# TLM_002_SRC.net
KiCad netlist of a schematic drawn in Altium Designer
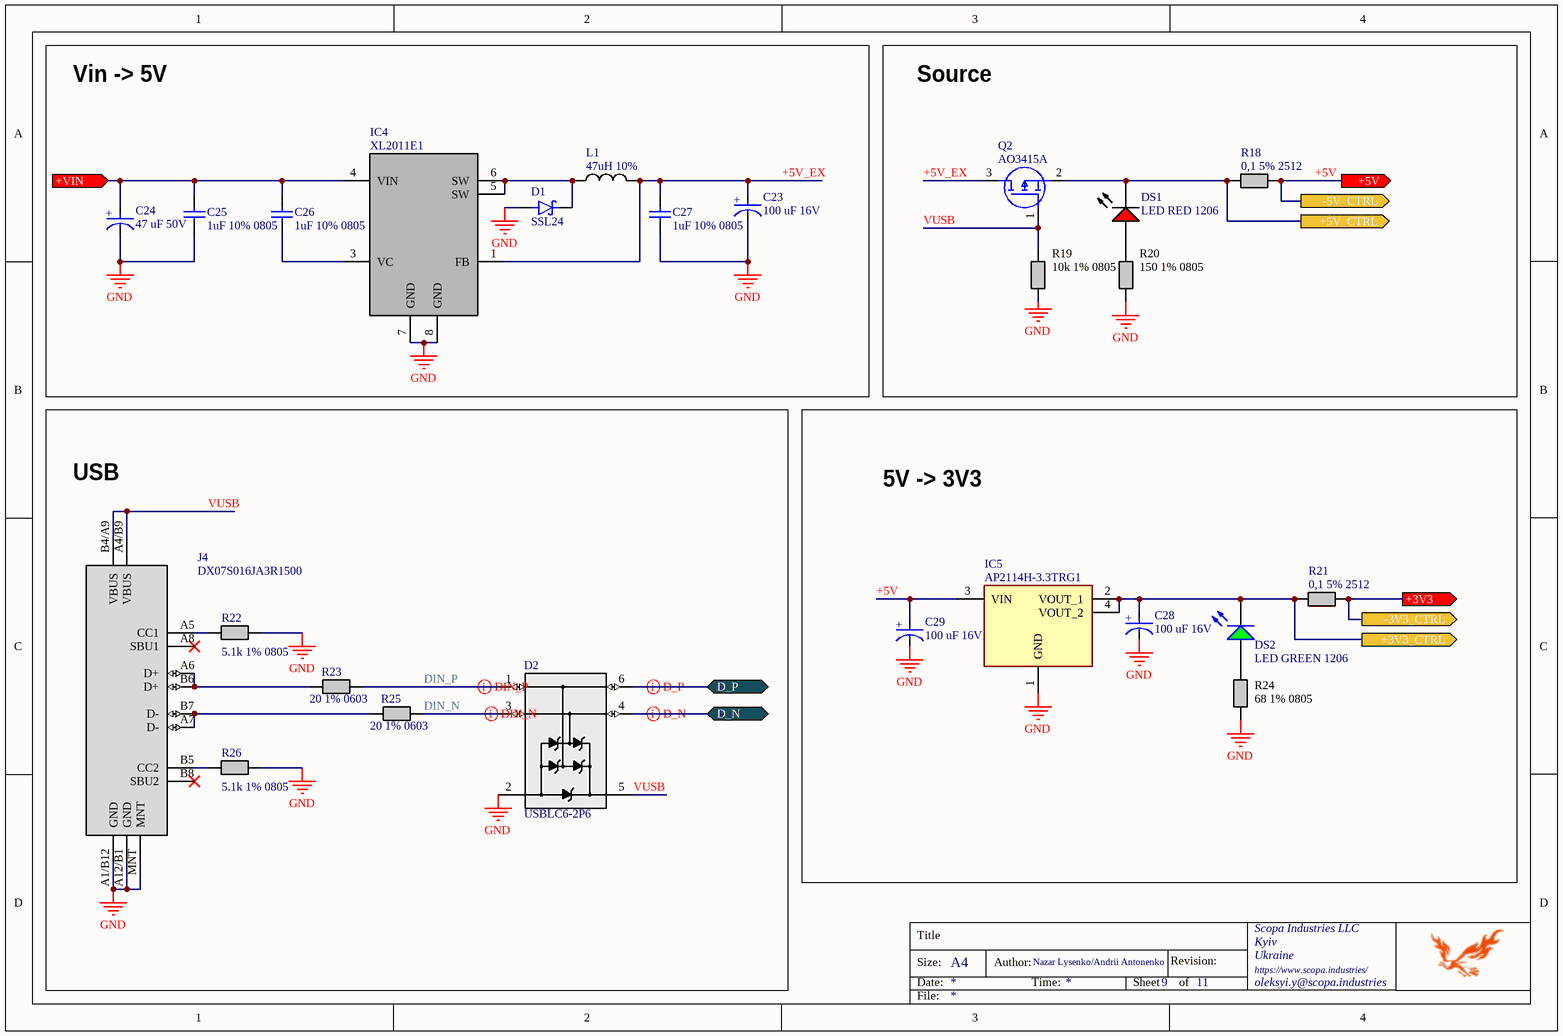
[diagram p0: TLM_002_SRC.SchDoc]

(export (version "E")
  (design (tool "Eeschema 10.0.6"))
  (components
    (comp (ref "C23")
      (value "100 uF 16V")
      (footprint "FP-ZLG6_3X11-MFG")
      (description "CAP ALUM 100UF 16V RADIAL")
      (fields (field (name "TOLERANCE") "20%"))
      (libsource (lib "Altium Content Vault") (part "a00bbbee19879c290e62620ae7e47b1"))
    )
    (comp (ref "C24")
      (value "47 uF 50V")
      (footprint "FP-ZLG6_3X11-MFG")
      (description "CAP ALUM 47UF 50V RADIAL")
      (fields (field (name "TOLERANCE") "20%"))
      (libsource (lib "Altium Content Vault") (part "a00bbbee19879c290e62620ae7e47b1"))
    )
    (comp (ref "C25")
      (value "1uF 10% 0805")
      (footprint "CAPC2013X145X50NL20T20")
      (fields (field (name "PART NUMBER") "VJ0805Y105KXQRW1BC") (field (name "MANUFACTURER") "Vitramon"))
      (libsource (lib "Altium Content Vault") (part "CAP"))
    )
    (comp (ref "C26")
      (value "1uF 10% 0805")
      (footprint "CAPC2013X145X50NL20T20")
      (fields (field (name "PART NUMBER") "VJ0805Y105KXQRW1BC") (field (name "MANUFACTURER") "Vitramon"))
      (libsource (lib "Altium Content Vault") (part "CAP"))
    )
    (comp (ref "C27")
      (value "1uF 10% 0805")
      (footprint "CAPC2013X145X50NL20T20")
      (fields (field (name "PART NUMBER") "VJ0805Y105KXQRW1BC") (field (name "MANUFACTURER") "Vitramon"))
      (libsource (lib "Altium Content Vault") (part "CAP"))
    )
    (comp (ref "C28")
      (value "100 uF 16V")
      (footprint "FP-ZLG6_3X11-MFG")
      (description "CAP ALUM 100UF 16V RADIAL")
      (fields (field (name "TOLERANCE") "20%"))
      (libsource (lib "Altium Content Vault") (part "a00bbbee19879c290e62620ae7e47b1"))
    )
    (comp (ref "C29")
      (value "100 uF 16V")
      (footprint "FP-ZLG6_3X11-MFG")
      (description "CAP ALUM 100UF 16V RADIAL")
      (fields (field (name "TOLERANCE") "20%"))
      (libsource (lib "Altium Content Vault") (part "a00bbbee19879c290e62620ae7e47b1"))
    )
    (comp (ref "D1")
      (value "SSL24")
      (footprint "DIO_SSL24")
      (description "2A, 40V, Schottky Rectifier")
      (fields (field (name "MF") "Taiwan Semiconductor"))
      (libsource (lib "SSL24") (part "SSL24"))
    )
    (comp (ref "D2")
      (value "USBLC6-2P6")
      (footprint "FP-SOT-666-MFG")
      (description "ESD Suppressors / TVS Diodes High Speed Interface Protection Low Cap")
      (libsource (lib "NAZAR LYSENKO") (part "c871e55f7e3243d341edbd671b98d92"))
    )
    (comp (ref "DS1")
      (value "LED RED 1206")
      (footprint "LUMX-SML-LX1206IC_V")
      (description "LED Red, 65 mW, -40 to 85 degC, 2-Pin SMD, RoHS, Tape and Reel")
      (fields (field (name "MANUFACTURER") "Lumex") (field (name "PART NO") "SML-LX1206IC-TR"))
      (libsource (lib "Altium Content Vault") (part "LED-RED-AK-2"))
    )
    (comp (ref "DS2")
      (value "LED GREEN 1206")
      (footprint "LTST-C230KGKT_V")
      (description "LED Green, 75 mW, 30 mA, -30 to 85 degC, 2-Pin SMD, RoHS, Tape and Reel")
      (fields (field (name "MANUFACTURER") "Lite-On"))
      (libsource (lib "Altium Content Vault") (part "LED-GREEN-AK-2"))
    )
    (comp (ref "IC4")
      (value "XL2011E1")
      (footprint "SOIC127P600X175-8N")
      (description "Integrated Circuit")
      (fields
        (field (name "MANUFACTURER_PART_NUMBER") "NE555DR")
        (field (name "MOUSER PART NUMBER") "595-NE555DR")
      )
      (libsource (lib "SamacSys") (part "XL2011E1"))
    )
    (comp (ref "IC5")
      (value "AP2114H-3.3TRG1")
      (footprint "SamacSys:SOT230P700X180-4N")
      (description "Integrated Circuit")
      (fields (field (name "MOUSER PART NUMBER") "621-AP2114H-3.3TRG1"))
      (libsource (lib "SamacSys") (part "AP2114H-3.3TRG1"))
    )
    (comp (ref "J4")
      (value "DX07S016JA3R1500")
      (footprint "FP-DX07S016JA3R1500-MFG")
      (description "Receptacle, 16 Position, 1-Row SMT, without Rear Shield, Shell-DIP Length 1.2mm")
      (libsource (lib "NAZAR LYSENKO") (part "86c7019cab7ffbad937e454fd6d8a8a"))
    )
    (comp (ref "L1")
      (value "47uH 10%")
      (footprint "INDUCTOR 9MM")
      (libsource (lib "Generic-Schematic-Library") (part "Inductor_470k"))
    )
    (comp (ref "Q2")
      (value "AO3415A")
      (footprint "SamacSys:SOT95P280X125-3N")
      (description "MOSFET (P-Channel)")
      (libsource (lib "*") (part "AO3415A"))
    )
    (comp (ref "R18")
      (value "0,1 5% 2512")
      (footprint "RES_2512")
      (description "Resistor 0,1 Ohm 5% SMD 2512 Generic")
      (fields (field (name "TOLERANCE") "1%"))
      (libsource (lib "Generic-Schematic-Library") (part "Resistor_0,1"))
    )
    (comp (ref "R19")
      (value "10k 1% 0805")
      (footprint "RES_0805")
      (description "Resistor 10kOhm 1% SMD 0805 Generic")
      (fields (field (name "TOLERANCE") "1%"))
      (libsource (lib "Generic-Schematic-Library") (part "Resistor_10k"))
    )
    (comp (ref "R20")
      (value "150 1% 0805")
      (footprint "RES_0805")
      (description "Resistor 150 Ohm 1% SMD 0805 Generic")
      (fields (field (name "TOLERANCE") "1%"))
      (libsource (lib "Generic-Schematic-Library") (part "Resistor_10k"))
    )
    (comp (ref "R21")
      (value "0,1 5% 2512")
      (footprint "RES_2512")
      (description "Resistor 0,1 Ohm 5% SMD 2512 Generic")
      (fields (field (name "TOLERANCE") "1%"))
      (libsource (lib "Generic-Schematic-Library") (part "Resistor_0,1"))
    )
    (comp (ref "R22")
      (value "5.1k 1% 0805")
      (footprint "RES_0805")
      (description "Resistor 5.1kOhm 1% SMD 0805 Generic")
      (fields (field (name "TOLERANCE") "1%"))
      (libsource (lib "Generic-Schematic-Library") (part "Resistor_1k"))
    )
    (comp (ref "R23")
      (value "20 1% 0603")
      (footprint "RES_0603")
      (description "Resistor 20Ohm 1% SMD 0603 Generic")
      (fields (field (name "TOLERANCE") "1%"))
      (libsource (lib "Generic-Schematic-Library") (part "Resistor_20"))
    )
    (comp (ref "R24")
      (value "68 1% 0805")
      (footprint "RES_0805")
      (description "Resistor 68 Ohm 1% SMD 0805 Generic")
      (fields (field (name "TOLERANCE") "1%"))
      (libsource (lib "Generic-Schematic-Library") (part "Resistor_10k"))
    )
    (comp (ref "R25")
      (value "20 1% 0603")
      (footprint "RES_0603")
      (description "Resistor 20Ohm 1% SMD 0603 Generic")
      (fields (field (name "TOLERANCE") "1%"))
      (libsource (lib "Generic-Schematic-Library") (part "Resistor_20"))
    )
    (comp (ref "R26")
      (value "5.1k 1% 0805")
      (footprint "RES_0805")
      (description "Resistor 5.1kOhm 1% SMD 0805 Generic")
      (fields (field (name "TOLERANCE") "1%"))
      (libsource (lib "Generic-Schematic-Library") (part "Resistor_1k"))
    )
  )
  (nets
    (net (code "1") (name "/+3V3") (class "Default")
      (node (ref "R21") (pin "1") (pinfunction "1_1") (pintype "passive"))
    )
    (net (code "2") (name "/+3V3_CTRL") (class "Default")
      (node (ref "C28") (pin "2") (pinfunction "A_2") (pintype "passive"))
      (node (ref "DS2") (pin "2") (pinfunction "K_2") (pintype "passive"))
      (node (ref "IC5") (pin "2") (pinfunction "VOUT_1_2") (pintype "passive"))
      (node (ref "IC5") (pin "4") (pinfunction "VOUT_2_4") (pintype "passive"))
      (node (ref "R21") (pin "2") (pinfunction "2_2") (pintype "passive"))
    )
    (net (code "3") (name "/+5V") (class "Default")
      (node (ref "C29") (pin "2") (pinfunction "A_2") (pintype "passive"))
      (node (ref "IC5") (pin "3") (pinfunction "VIN_3") (pintype "passive"))
      (node (ref "R18") (pin "1") (pinfunction "1_1") (pintype "passive"))
    )
    (net (code "4") (name "/+5V_CTRL") (class "Default")
      (node (ref "DS1") (pin "2") (pinfunction "K_2") (pintype "passive"))
      (node (ref "Q2") (pin "2") (pinfunction "S_2") (pintype "passive"))
      (node (ref "R18") (pin "2") (pinfunction "2_2") (pintype "passive"))
    )
    (net (code "5") (name "/+5V_EX") (class "Default")
      (node (ref "C23") (pin "2") (pinfunction "A_2") (pintype "passive"))
      (node (ref "C27") (pin "2") (pinfunction "2_2") (pintype "passive"))
      (node (ref "IC4") (pin "1") (pinfunction "FB_1") (pintype "power_in"))
      (node (ref "L1") (pin "2") (pinfunction "2_2") (pintype "passive"))
      (node (ref "Q2") (pin "3") (pinfunction "D_3") (pintype "passive"))
    )
    (net (code "6") (name "/+VIN") (class "Default")
      (node (ref "C24") (pin "2") (pinfunction "A_2") (pintype "passive"))
      (node (ref "C25") (pin "2") (pinfunction "2_2") (pintype "passive"))
      (node (ref "C26") (pin "2") (pinfunction "2_2") (pintype "passive"))
      (node (ref "IC4") (pin "4") (pinfunction "VIN_4") (pintype "passive"))
    )
    (net (code "7") (name "/DIN_N") (class "Default")
      (node (ref "D2") (pin "3") (pinfunction "I/O2_3") (pintype "bidirectional"))
      (node (ref "R25") (pin "2") (pinfunction "2_2") (pintype "passive"))
    )
    (net (code "8") (name "/DIN_P") (class "Default")
      (node (ref "D2") (pin "1") (pinfunction "I/O1_1") (pintype "bidirectional"))
      (node (ref "R23") (pin "2") (pinfunction "2_2") (pintype "passive"))
    )
    (net (code "9") (name "/D_N") (class "Default")
      (node (ref "D2") (pin "4") (pinfunction "I/O2_4") (pintype "bidirectional"))
    )
    (net (code "10") (name "/D_P") (class "Default")
      (node (ref "D2") (pin "6") (pinfunction "I/O1_6") (pintype "bidirectional"))
    )
    (net (code "11") (name "/VUSB") (class "Default")
      (node (ref "D2") (pin "5") (pinfunction "VBUS_5") (pintype "power_in"))
      (node (ref "J4") (pin "A4/B9") (pinfunction "VBUS_A4/B9") (pintype "power_in"))
      (node (ref "J4") (pin "B4/A9") (pinfunction "VBUS_B4/A9") (pintype "power_in"))
      (node (ref "Q2") (pin "1") (pinfunction "G_1") (pintype "passive"))
      (node (ref "R19") (pin "1") (pinfunction "1_1") (pintype "passive"))
    )
    (net (code "12") (name "GND") (class "Default")
      (node (ref "C23") (pin "1") (pinfunction "C_1") (pintype "passive"))
      (node (ref "C24") (pin "1") (pinfunction "C_1") (pintype "passive"))
      (node (ref "C25") (pin "1") (pinfunction "1_1") (pintype "passive"))
      (node (ref "C27") (pin "1") (pinfunction "1_1") (pintype "passive"))
      (node (ref "C28") (pin "1") (pinfunction "C_1") (pintype "passive"))
      (node (ref "C29") (pin "1") (pinfunction "C_1") (pintype "passive"))
      (node (ref "D1") (pin "A") (pinfunction "A_A") (pintype "passive"))
      (node (ref "D2") (pin "2") (pinfunction "GND_2") (pintype "power_in"))
      (node (ref "IC4") (pin "7") (pinfunction "GND_7") (pintype "passive"))
      (node (ref "IC4") (pin "8") (pinfunction "GND_8") (pintype "power_in"))
      (node (ref "IC5") (pin "1") (pinfunction "GND_1") (pintype "passive"))
      (node (ref "J4") (pin "A1/B12") (pinfunction "GND_A1/B12") (pintype "power_in"))
      (node (ref "J4") (pin "A12/B1") (pinfunction "GND_A12/B1") (pintype "power_in"))
      (node (ref "J4") (pin "MNT") (pinfunction "MNT_MNT") (pintype "passive"))
      (node (ref "R19") (pin "2") (pinfunction "2_2") (pintype "passive"))
      (node (ref "R20") (pin "2") (pinfunction "2_2") (pintype "passive"))
      (node (ref "R22") (pin "1") (pinfunction "1_1") (pintype "passive"))
      (node (ref "R24") (pin "2") (pinfunction "2_2") (pintype "passive"))
      (node (ref "R26") (pin "1") (pinfunction "1_1") (pintype "passive"))
    )
    (net (code "13") (name "Net-(D1-K)") (class "Default")
      (node (ref "D1") (pin "C") (pinfunction "K_C") (pintype "passive"))
      (node (ref "IC4") (pin "5") (pinfunction "SW_5") (pintype "passive"))
      (node (ref "IC4") (pin "6") (pinfunction "SW_6") (pintype "passive"))
      (node (ref "L1") (pin "1") (pinfunction "1_1") (pintype "passive"))
    )
    (net (code "14") (name "Net-(DS1-A)") (class "Default")
      (node (ref "DS1") (pin "1") (pinfunction "A_1") (pintype "passive"))
      (node (ref "R20") (pin "1") (pinfunction "1_1") (pintype "passive"))
    )
    (net (code "15") (name "Net-(DS2-A)") (class "Default")
      (node (ref "DS2") (pin "1") (pinfunction "A_1") (pintype "passive"))
      (node (ref "R24") (pin "1") (pinfunction "1_1") (pintype "passive"))
    )
    (net (code "16") (name "Net-(IC4-VC)") (class "Default")
      (node (ref "C26") (pin "1") (pinfunction "1_1") (pintype "passive"))
      (node (ref "IC4") (pin "3") (pinfunction "VC_3") (pintype "passive"))
    )
    (net (code "17") (name "Net-(J4-CC1)") (class "Default")
      (node (ref "J4") (pin "A5") (pinfunction "CC1_A5") (pintype "passive"))
      (node (ref "R22") (pin "2") (pinfunction "2_2") (pintype "passive"))
    )
    (net (code "18") (name "Net-(J4-CC2)") (class "Default")
      (node (ref "J4") (pin "B5") (pinfunction "CC2_B5") (pintype "passive"))
      (node (ref "R26") (pin "2") (pinfunction "2_2") (pintype "passive"))
    )
    (net (code "19") (name "Net-(J4-D+-PadA6)") (class "Default")
      (node (ref "J4") (pin "A6") (pinfunction "D+_A6") (pintype "bidirectional"))
      (node (ref "J4") (pin "B6") (pinfunction "D+_B6") (pintype "bidirectional"))
      (node (ref "R23") (pin "1") (pinfunction "1_1") (pintype "passive"))
    )
    (net (code "20") (name "Net-(J4-D--PadA7)") (class "Default")
      (node (ref "J4") (pin "A7") (pinfunction "D-_A7") (pintype "bidirectional"))
      (node (ref "J4") (pin "B7") (pinfunction "D-_B7") (pintype "bidirectional"))
      (node (ref "R25") (pin "1") (pinfunction "1_1") (pintype "passive"))
    )
    (net (code "21") (name "unconnected-(J4-SBU1-PadA8)") (class "Default")
      (node (ref "J4") (pin "A8") (pinfunction "SBU1_A8") (pintype "passive+no_connect"))
    )
    (net (code "22") (name "unconnected-(J4-SBU2-PadB8)") (class "Default")
      (node (ref "J4") (pin "B8") (pinfunction "SBU2_B8") (pintype "passive+no_connect"))
    )
  )
)
